# Optical_Switch_PCB.net
KiCad netlist of a schematic drawn in Altium Designer
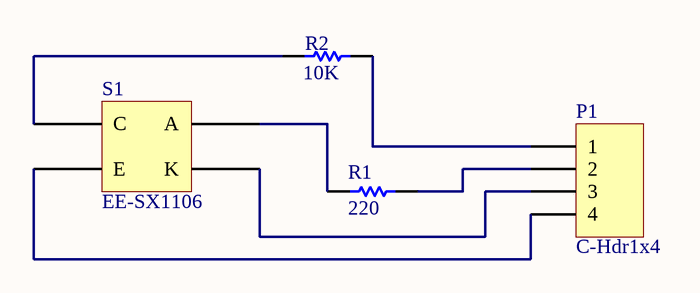
[diagram p0: Optical Switch PCB.SchDoc]

(export (version "E")
  (design (tool "Eeschema 10.0.6"))
  (components
    (comp (ref "P1")
      (value "C-Hdr1x4")
      (footprint "HDR1X4_LGE1.0")
      (description "Header, 4-Pin")
      (fields (field (name "PUBLISHER") "Altium Limited"))
      (libsource (lib "PartsDatabaseV13p1") (part "C-Hdr1x4"))
    )
    (comp (ref "R1")
      (value "220")
      (footprint "AXIAL-0.3")
      (description "Resistor")
      (fields (field (name "PUBLISHER") "Altium Limited"))
      (libsource (lib "Miscellaneous Devices") (part "Res1"))
    )
    (comp (ref "R2")
      (value "10K")
      (footprint "AXIAL-0.3")
      (description "Resistor")
      (fields (field (name "PUBLISHER") "Altium Limited"))
      (libsource (lib "Miscellaneous Devices") (part "Res1"))
    )
    (comp (ref "S1")
      (value "EE-SX1106")
      (footprint "S-OptSw")
      (description "Optical Switch")
      (libsource (lib "PartsDatabaseV13p1") (part "S-OptSw"))
    )
  )
  (nets
    (net (code "1") (name "Net-(P1-Pad1)") (class "Default")
      (node (ref "P1") (pin "1") (pinfunction "1_1") (pintype "passive"))
      (node (ref "R2") (pin "2") (pinfunction "2_2") (pintype "passive"))
    )
    (net (code "2") (name "Net-(P1-Pad2)") (class "Default")
      (node (ref "P1") (pin "2") (pinfunction "2_2") (pintype "passive"))
      (node (ref "R1") (pin "2") (pinfunction "2_2") (pintype "passive"))
    )
    (net (code "3") (name "Net-(P1-Pad3)") (class "Default")
      (node (ref "P1") (pin "3") (pinfunction "3_3") (pintype "passive"))
      (node (ref "S1") (pin "K") (pinfunction "K_K") (pintype "passive"))
    )
    (net (code "4") (name "Net-(P1-Pad4)") (class "Default")
      (node (ref "P1") (pin "4") (pinfunction "4_4") (pintype "passive"))
      (node (ref "S1") (pin "E") (pinfunction "E_E") (pintype "passive"))
    )
    (net (code "5") (name "Net-(R1-Pad1)") (class "Default")
      (node (ref "R1") (pin "1") (pinfunction "1_1") (pintype "passive"))
      (node (ref "S1") (pin "A") (pinfunction "A_A") (pintype "passive"))
    )
    (net (code "6") (name "Net-(R2-Pad1)") (class "Default")
      (node (ref "R2") (pin "1") (pinfunction "1_1") (pintype "passive"))
      (node (ref "S1") (pin "C") (pinfunction "C_C") (pintype "passive"))
    )
  )
)
